# TransientsVCFG_half.net
KiCad netlist of a schematic drawn in EAGLE
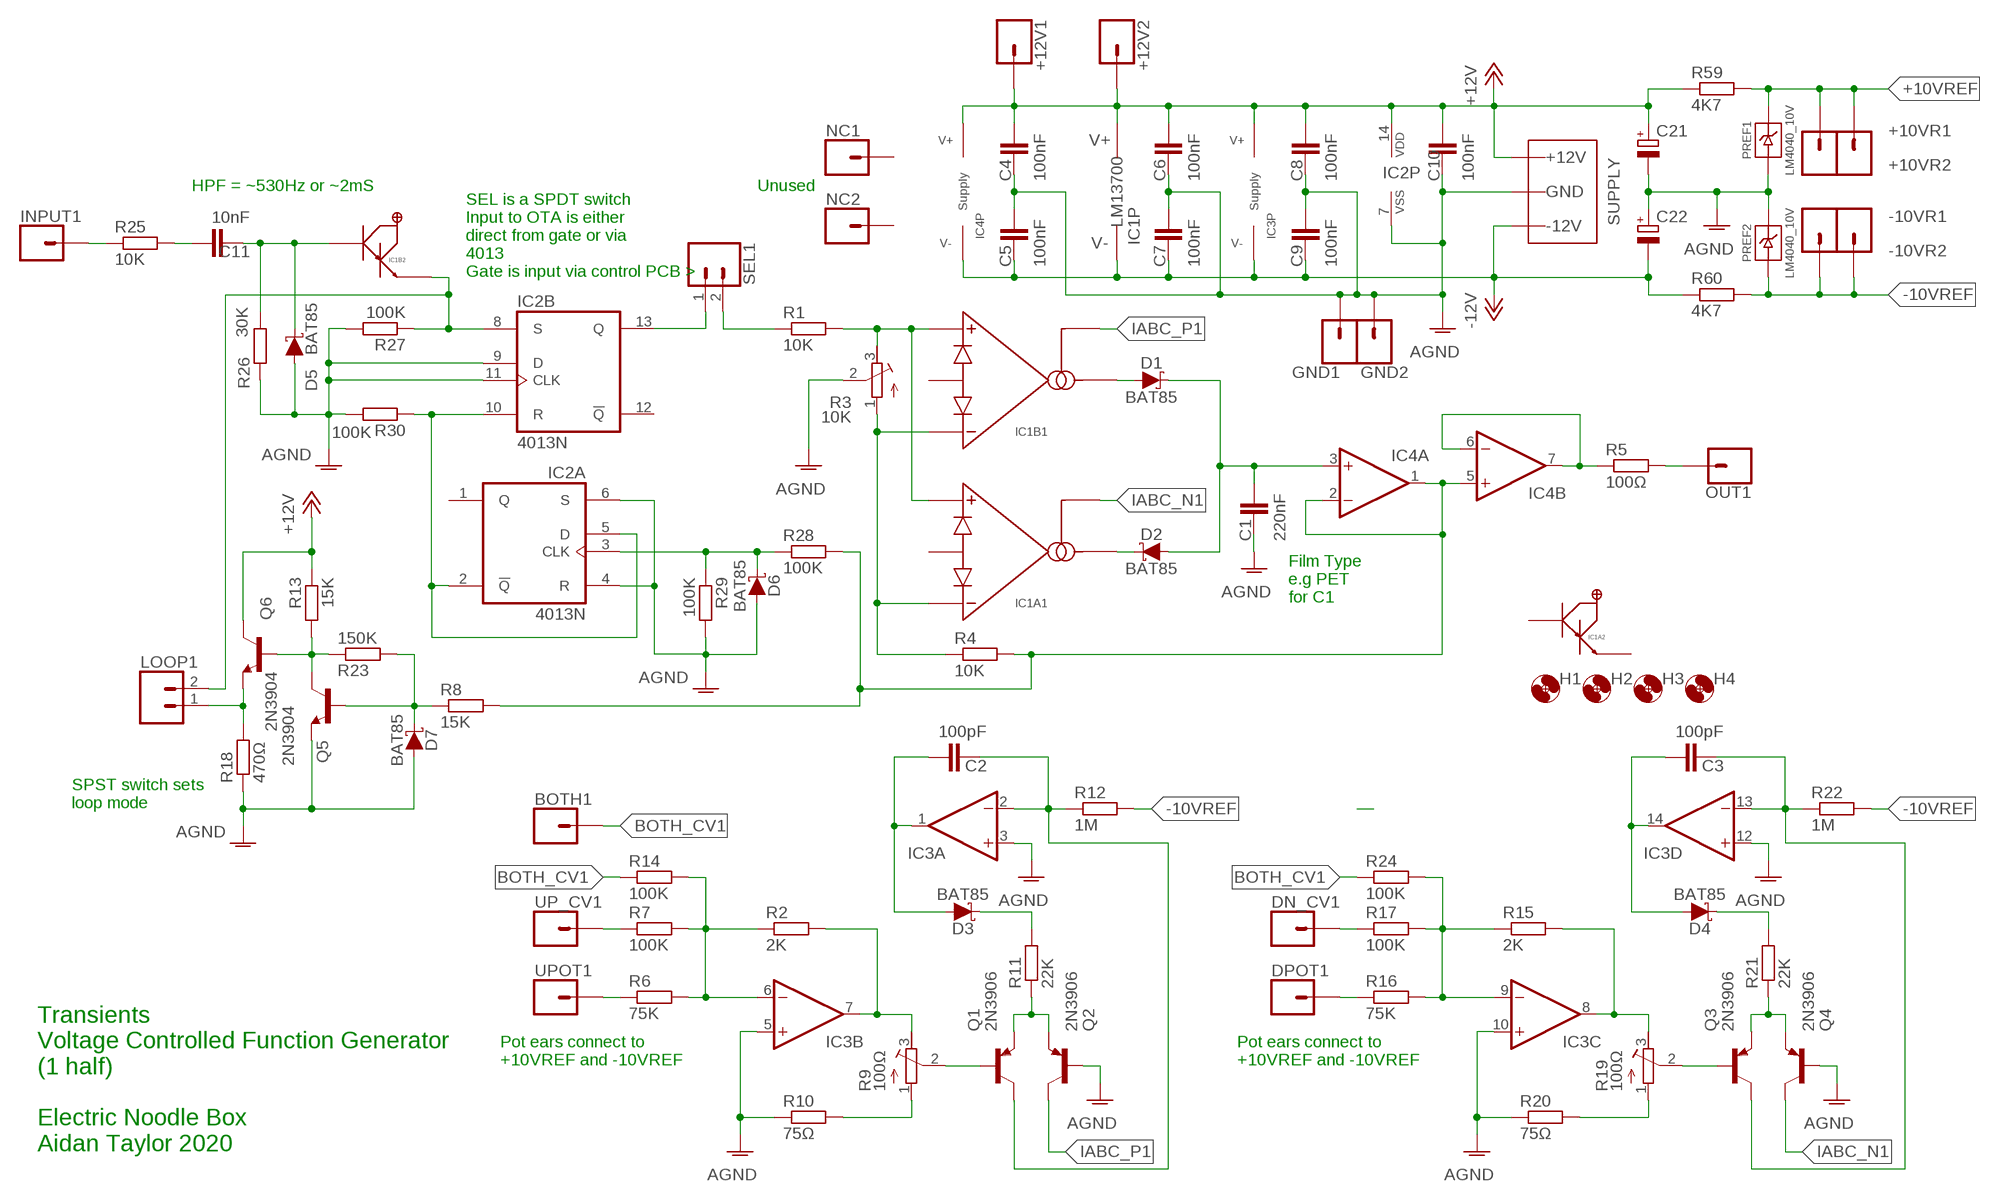
[diagram p0: schematic, sheet 1]

(export (version "E")
  (design (tool "Eeschema 10.0.6"))
  (components
    (comp (ref "+10VR1")
      (value "1XWIREPAD")
      (footprint "eagle-import:1X01")
      (libsource (lib "eagle-import") (part "1XWIREPAD"))
    )
    (comp (ref "+10VR2")
      (value "1XWIREPAD")
      (footprint "eagle-import:1X01")
      (libsource (lib "eagle-import") (part "1XWIREPAD"))
    )
    (comp (ref "+12V1")
      (value "1XWIREPAD")
      (footprint "eagle-import:1X01")
      (libsource (lib "eagle-import") (part "1XWIREPAD"))
    )
    (comp (ref "+12V2")
      (value "1XWIREPAD")
      (footprint "eagle-import:1X01")
      (libsource (lib "eagle-import") (part "1XWIREPAD"))
    )
    (comp (ref "-10VR1")
      (value "1XWIREPAD")
      (footprint "eagle-import:1X01")
      (libsource (lib "eagle-import") (part "1XWIREPAD"))
    )
    (comp (ref "-10VR2")
      (value "1XWIREPAD")
      (footprint "eagle-import:1X01")
      (libsource (lib "eagle-import") (part "1XWIREPAD"))
    )
    (comp (ref "BOTH1")
      (value "1XWIREPAD")
      (footprint "eagle-import:1X01")
      (libsource (lib "eagle-import") (part "1XWIREPAD"))
    )
    (comp (ref "C1")
      (value "220nF")
      (footprint "eagle-import:C050-025X075")
      (libsource (lib "eagle-import") (part "C-EU050-025X075"))
    )
    (comp (ref "C2")
      (value "100pF")
      (footprint "eagle-import:C050-025X075")
      (libsource (lib "eagle-import") (part "C-EU050-025X075"))
    )
    (comp (ref "C3")
      (value "100pF")
      (footprint "eagle-import:C050-025X075")
      (libsource (lib "eagle-import") (part "C-EU050-025X075"))
    )
    (comp (ref "C4")
      (value "100nF")
      (footprint "eagle-import:C050-025X075")
      (libsource (lib "eagle-import") (part "C-EU050-025X075"))
    )
    (comp (ref "C5")
      (value "100nF")
      (footprint "eagle-import:C050-025X075")
      (libsource (lib "eagle-import") (part "C-EU050-025X075"))
    )
    (comp (ref "C6")
      (value "100nF")
      (footprint "eagle-import:C050-025X075")
      (libsource (lib "eagle-import") (part "C-EU050-025X075"))
    )
    (comp (ref "C7")
      (value "100nF")
      (footprint "eagle-import:C050-025X075")
      (libsource (lib "eagle-import") (part "C-EU050-025X075"))
    )
    (comp (ref "C8")
      (value "100nF")
      (footprint "eagle-import:C050-025X075")
      (libsource (lib "eagle-import") (part "C-EU050-025X075"))
    )
    (comp (ref "C9")
      (value "100nF")
      (footprint "eagle-import:C050-025X075")
      (libsource (lib "eagle-import") (part "C-EU050-025X075"))
    )
    (comp (ref "C10")
      (value "100nF")
      (footprint "eagle-import:C050-025X075")
      (libsource (lib "eagle-import") (part "C-EU050-025X075"))
    )
    (comp (ref "C11")
      (value "10nF")
      (footprint "eagle-import:C050-025X075")
      (libsource (lib "eagle-import") (part "C-EU050-025X075"))
    )
    (comp (ref "C21")
      (value "CPOL-EUE2.5-6")
      (footprint "eagle-import:E2,5-6")
      (libsource (lib "eagle-import") (part "CPOL-EUE2.5-6"))
    )
    (comp (ref "C22")
      (value "CPOL-EUE2.5-6")
      (footprint "eagle-import:E2,5-6")
      (libsource (lib "eagle-import") (part "CPOL-EUE2.5-6"))
    )
    (comp (ref "D1")
      (value "BAT85")
      (footprint "eagle-import:DO35-7")
      (libsource (lib "eagle-import") (part "SCHOTTKY_DO35"))
    )
    (comp (ref "D2")
      (value "BAT85")
      (footprint "eagle-import:DO35-7")
      (libsource (lib "eagle-import") (part "SCHOTTKY_DO35"))
    )
    (comp (ref "D3")
      (value "BAT85")
      (footprint "eagle-import:DO35-7")
      (libsource (lib "eagle-import") (part "SCHOTTKY_DO35"))
    )
    (comp (ref "D4")
      (value "BAT85")
      (footprint "eagle-import:DO35-7")
      (libsource (lib "eagle-import") (part "SCHOTTKY_DO35"))
    )
    (comp (ref "D5")
      (value "BAT85")
      (footprint "eagle-import:DO35-7")
      (libsource (lib "eagle-import") (part "SCHOTTKY_DO35"))
    )
    (comp (ref "D6")
      (value "BAT85")
      (footprint "eagle-import:DO35-7")
      (libsource (lib "eagle-import") (part "SCHOTTKY_DO35"))
    )
    (comp (ref "D7")
      (value "BAT85")
      (footprint "eagle-import:DO35-7")
      (libsource (lib "eagle-import") (part "SCHOTTKY_DO35"))
    )
    (comp (ref "DN_CV1")
      (value "1XWIREPAD")
      (footprint "eagle-import:1X01")
      (libsource (lib "eagle-import") (part "1XWIREPAD"))
    )
    (comp (ref "DPOT1")
      (value "1XWIREPAD")
      (footprint "eagle-import:1X01")
      (libsource (lib "eagle-import") (part "1XWIREPAD"))
    )
    (comp (ref "GND1")
      (value "1XWIREPAD")
      (footprint "eagle-import:1X01")
      (libsource (lib "eagle-import") (part "1XWIREPAD"))
    )
    (comp (ref "GND2")
      (value "1XWIREPAD")
      (footprint "eagle-import:1X01")
      (libsource (lib "eagle-import") (part "1XWIREPAD"))
    )
    (comp (ref "H1")
      (value "MOUNT-HOLE3.2")
      (footprint "eagle-import:3,2")
      (libsource (lib "eagle-import") (part "MOUNT-HOLE3.2"))
    )
    (comp (ref "H2")
      (value "MOUNT-HOLE3.2")
      (footprint "eagle-import:3,2")
      (libsource (lib "eagle-import") (part "MOUNT-HOLE3.2"))
    )
    (comp (ref "H3")
      (value "MOUNT-HOLE3.2")
      (footprint "eagle-import:3,2")
      (libsource (lib "eagle-import") (part "MOUNT-HOLE3.2"))
    )
    (comp (ref "H4")
      (value "MOUNT-HOLE3.2")
      (footprint "eagle-import:3,2")
      (libsource (lib "eagle-import") (part "MOUNT-HOLE3.2"))
    )
    (comp (ref "IC1")
      (value "LM13700DIL")
      (footprint "eagle-import:DIL16")
      (libsource (lib "eagle-import") (part "LM13700DIL"))
    )
    (comp (ref "IC2")
      (value "4013N")
      (footprint "eagle-import:DIL14")
      (libsource (lib "eagle-import") (part "4013N"))
    )
    (comp (ref "IC3")
      (value "TL0X4DIL")
      (footprint "eagle-import:DIL14")
      (libsource (lib "eagle-import") (part "TL0X4DIL"))
    )
    (comp (ref "IC4")
      (value "TL0X2DIL")
      (footprint "eagle-import:DIL08")
      (libsource (lib "eagle-import") (part "TL0X2DIL"))
    )
    (comp (ref "INPUT1")
      (value "1XWIREPAD")
      (footprint "eagle-import:1X01")
      (libsource (lib "eagle-import") (part "1XWIREPAD"))
    )
    (comp (ref "LOOP1")
      (value "2XWIREPAD")
      (footprint "eagle-import:1X02")
      (libsource (lib "eagle-import") (part "2XWIREPAD"))
    )
    (comp (ref "NC1")
      (value "1XWIREPAD")
      (footprint "eagle-import:1X01")
      (libsource (lib "eagle-import") (part "1XWIREPAD"))
    )
    (comp (ref "NC2")
      (value "1XWIREPAD")
      (footprint "eagle-import:1X01")
      (libsource (lib "eagle-import") (part "1XWIREPAD"))
    )
    (comp (ref "OUT1")
      (value "1XWIREPAD")
      (footprint "eagle-import:1X01")
      (libsource (lib "eagle-import") (part "1XWIREPAD"))
    )
    (comp (ref "PREF1")
      (value "LM4040_10V")
      (footprint "eagle-import:TO92")
      (libsource (lib "eagle-import") (part "LM4040TH"))
    )
    (comp (ref "PREF2")
      (value "LM4040_10V")
      (footprint "eagle-import:TO92")
      (libsource (lib "eagle-import") (part "LM4040TH"))
    )
    (comp (ref "Q1")
      (value "2N3906")
      (footprint "eagle-import:TO92")
      (libsource (lib "eagle-import") (part "2N3906"))
    )
    (comp (ref "Q2")
      (value "2N3906")
      (footprint "eagle-import:TO92")
      (libsource (lib "eagle-import") (part "2N3906"))
    )
    (comp (ref "Q3")
      (value "2N3906")
      (footprint "eagle-import:TO92")
      (libsource (lib "eagle-import") (part "2N3906"))
    )
    (comp (ref "Q4")
      (value "2N3906")
      (footprint "eagle-import:TO92")
      (libsource (lib "eagle-import") (part "2N3906"))
    )
    (comp (ref "Q5")
      (value "2N3904")
      (footprint "eagle-import:TO92")
      (libsource (lib "eagle-import") (part "2N3904"))
    )
    (comp (ref "Q6")
      (value "2N3904")
      (footprint "eagle-import:TO92")
      (libsource (lib "eagle-import") (part "2N3904"))
    )
    (comp (ref "R1")
      (value "10K")
      (footprint "eagle-import:0207_10")
      (libsource (lib "eagle-import") (part "R-EU_0207/10"))
    )
    (comp (ref "R2")
      (value "2K")
      (footprint "eagle-import:0207_10")
      (libsource (lib "eagle-import") (part "R-EU_0207/10"))
    )
    (comp (ref "R3")
      (value "10K")
      (footprint "eagle-import:RTRIM3296W")
      (libsource (lib "eagle-import") (part "R-TRIMM3296W"))
    )
    (comp (ref "R4")
      (value "10K")
      (footprint "eagle-import:0207_10")
      (libsource (lib "eagle-import") (part "R-EU_0207/10"))
    )
    (comp (ref "R5")
      (value "100Ω")
      (footprint "eagle-import:0207_10")
      (libsource (lib "eagle-import") (part "R-EU_0207/10"))
    )
    (comp (ref "R6")
      (value "75K")
      (footprint "eagle-import:0207_10")
      (libsource (lib "eagle-import") (part "R-EU_0207/10"))
    )
    (comp (ref "R7")
      (value "100K")
      (footprint "eagle-import:0207_10")
      (libsource (lib "eagle-import") (part "R-EU_0207/10"))
    )
    (comp (ref "R8")
      (value "15K")
      (footprint "eagle-import:0207_10")
      (libsource (lib "eagle-import") (part "R-EU_0207/10"))
    )
    (comp (ref "R9")
      (value "100Ω")
      (footprint "eagle-import:RTRIM3296W")
      (libsource (lib "eagle-import") (part "R-TRIMM3296W"))
    )
    (comp (ref "R10")
      (value "75Ω")
      (footprint "eagle-import:0207_10")
      (libsource (lib "eagle-import") (part "R-EU_0207/10"))
    )
    (comp (ref "R11")
      (value "22K")
      (footprint "eagle-import:0207_10")
      (libsource (lib "eagle-import") (part "R-EU_0207/10"))
    )
    (comp (ref "R12")
      (value "1M")
      (footprint "eagle-import:0207_10")
      (libsource (lib "eagle-import") (part "R-EU_0207/10"))
    )
    (comp (ref "R13")
      (value "15K")
      (footprint "eagle-import:0207_10")
      (libsource (lib "eagle-import") (part "R-EU_0207/10"))
    )
    (comp (ref "R14")
      (value "100K")
      (footprint "eagle-import:0207_10")
      (libsource (lib "eagle-import") (part "R-EU_0207/10"))
    )
    (comp (ref "R15")
      (value "2K")
      (footprint "eagle-import:0207_10")
      (libsource (lib "eagle-import") (part "R-EU_0207/10"))
    )
    (comp (ref "R16")
      (value "75K")
      (footprint "eagle-import:0207_10")
      (libsource (lib "eagle-import") (part "R-EU_0207/10"))
    )
    (comp (ref "R17")
      (value "100K")
      (footprint "eagle-import:0207_10")
      (libsource (lib "eagle-import") (part "R-EU_0207/10"))
    )
    (comp (ref "R18")
      (value "470Ω")
      (footprint "eagle-import:0207_10")
      (libsource (lib "eagle-import") (part "R-EU_0207/10"))
    )
    (comp (ref "R19")
      (value "100Ω")
      (footprint "eagle-import:RTRIM3296W")
      (libsource (lib "eagle-import") (part "R-TRIMM3296W"))
    )
    (comp (ref "R20")
      (value "75Ω")
      (footprint "eagle-import:0207_10")
      (libsource (lib "eagle-import") (part "R-EU_0207/10"))
    )
    (comp (ref "R21")
      (value "22K")
      (footprint "eagle-import:0207_10")
      (libsource (lib "eagle-import") (part "R-EU_0207/10"))
    )
    (comp (ref "R22")
      (value "1M")
      (footprint "eagle-import:0207_10")
      (libsource (lib "eagle-import") (part "R-EU_0207/10"))
    )
    (comp (ref "R23")
      (value "150K")
      (footprint "eagle-import:0207_10")
      (libsource (lib "eagle-import") (part "R-EU_0207/10"))
    )
    (comp (ref "R24")
      (value "100K")
      (footprint "eagle-import:0207_10")
      (libsource (lib "eagle-import") (part "R-EU_0207/10"))
    )
    (comp (ref "R25")
      (value "10K")
      (footprint "eagle-import:0207_10")
      (libsource (lib "eagle-import") (part "R-EU_0207/10"))
    )
    (comp (ref "R26")
      (value "30K")
      (footprint "eagle-import:0207_10")
      (libsource (lib "eagle-import") (part "R-EU_0207/10"))
    )
    (comp (ref "R27")
      (value "100K")
      (footprint "eagle-import:0207_10")
      (libsource (lib "eagle-import") (part "R-EU_0207/10"))
    )
    (comp (ref "R28")
      (value "100K")
      (footprint "eagle-import:0207_10")
      (libsource (lib "eagle-import") (part "R-EU_0207/10"))
    )
    (comp (ref "R29")
      (value "100K")
      (footprint "eagle-import:0207_10")
      (libsource (lib "eagle-import") (part "R-EU_0207/10"))
    )
    (comp (ref "R30")
      (value "100K")
      (footprint "eagle-import:0207_10")
      (libsource (lib "eagle-import") (part "R-EU_0207/10"))
    )
    (comp (ref "R59")
      (value "4K7")
      (footprint "eagle-import:0207_10")
      (libsource (lib "eagle-import") (part "R-EU_0207/10"))
    )
    (comp (ref "R60")
      (value "4K7")
      (footprint "eagle-import:0207_10")
      (libsource (lib "eagle-import") (part "R-EU_0207/10"))
    )
    (comp (ref "SEL1")
      (value "2XWIREPAD")
      (footprint "eagle-import:1X02")
      (libsource (lib "eagle-import") (part "2XWIREPAD"))
    )
    (comp (ref "UPOT1")
      (value "1XWIREPAD")
      (footprint "eagle-import:1X01")
      (libsource (lib "eagle-import") (part "1XWIREPAD"))
    )
    (comp (ref "UP_CV1")
      (value "1XWIREPAD")
      (footprint "eagle-import:1X01")
      (libsource (lib "eagle-import") (part "1XWIREPAD"))
    )
    (comp (ref "WP1")
      (value "COMBO_SUPPLY_HEADER")
      (footprint "eagle-import:COMBINED_POWER")
      (libsource (lib "eagle-import") (part "COMBO_SUPPLY_HEADER"))
    )
  )
  (nets
    (net (code "1") (name "+10VREF") (class "Default")
      (node (ref "+10VR1") (pin "1") (pinfunction "1_1") (pintype "passive"))
      (node (ref "+10VR2") (pin "1") (pinfunction "1_1") (pintype "passive"))
      (node (ref "PREF1") (pin "2") (pinfunction "CATHODE_2") (pintype "power_in"))
      (node (ref "R59") (pin "2") (pinfunction "2_2") (pintype "passive"))
    )
    (net (code "2") (name "+12V") (class "Default")
      (node (ref "+12V1") (pin "1") (pinfunction "1_1") (pintype "passive"))
      (node (ref "+12V2") (pin "1") (pinfunction "1_1") (pintype "passive"))
      (node (ref "C10") (pin "1") (pinfunction "1_1") (pintype "passive"))
      (node (ref "C21") (pin "+") (pinfunction "+_+") (pintype "passive"))
      (node (ref "C4") (pin "1") (pinfunction "1_1") (pintype "passive"))
      (node (ref "C6") (pin "1") (pinfunction "1_1") (pintype "passive"))
      (node (ref "C8") (pin "1") (pinfunction "1_1") (pintype "passive"))
      (node (ref "IC1") (pin "11") (pinfunction "V+_11") (pintype "power_in"))
      (node (ref "IC2") (pin "14") (pinfunction "VDD_14") (pintype "power_in"))
      (node (ref "IC3") (pin "4") (pinfunction "V+_4") (pintype "bidirectional"))
      (node (ref "IC4") (pin "8") (pinfunction "V+_8") (pintype "bidirectional"))
      (node (ref "Q6") (pin "1") (pinfunction "C_1") (pintype "passive"))
      (node (ref "R13") (pin "1") (pinfunction "1_1") (pintype "passive"))
      (node (ref "R59") (pin "1") (pinfunction "1_1") (pintype "passive"))
      (node (ref "WP1") (pin "V+1") (pinfunction "V++_V+1") (pintype "power_in"))
      (node (ref "WP1") (pin "V+2") (pinfunction "V++_V+2") (pintype "power_in"))
      (node (ref "WP1") (pin "V+3") (pinfunction "V++_V+3") (pintype "power_in"))
    )
    (net (code "3") (name "-10VREF") (class "Default")
      (node (ref "-10VR1") (pin "1") (pinfunction "1_1") (pintype "passive"))
      (node (ref "-10VR2") (pin "1") (pinfunction "1_1") (pintype "passive"))
      (node (ref "PREF2") (pin "3") (pinfunction "ANODE_3") (pintype "power_in"))
      (node (ref "R12") (pin "2") (pinfunction "2_2") (pintype "passive"))
      (node (ref "R22") (pin "2") (pinfunction "2_2") (pintype "passive"))
      (node (ref "R60") (pin "2") (pinfunction "2_2") (pintype "passive"))
    )
    (net (code "4") (name "-12V") (class "Default")
      (node (ref "C22") (pin "-") (pinfunction "-_-") (pintype "passive"))
      (node (ref "C5") (pin "2") (pinfunction "2_2") (pintype "passive"))
      (node (ref "C7") (pin "2") (pinfunction "2_2") (pintype "passive"))
      (node (ref "C9") (pin "2") (pinfunction "2_2") (pintype "passive"))
      (node (ref "IC1") (pin "6") (pinfunction "V-_6") (pintype "power_in"))
      (node (ref "IC3") (pin "11") (pinfunction "V-_11") (pintype "bidirectional"))
      (node (ref "IC4") (pin "4") (pinfunction "V-_4") (pintype "bidirectional"))
      (node (ref "R60") (pin "1") (pinfunction "1_1") (pintype "passive"))
      (node (ref "WP1") (pin "V-1") (pinfunction "V--_V-1") (pintype "power_in"))
      (node (ref "WP1") (pin "V-2") (pinfunction "V--_V-2") (pintype "power_in"))
      (node (ref "WP1") (pin "V-3") (pinfunction "V--_V-3") (pintype "power_in"))
    )
    (net (code "5") (name "AGND") (class "Default")
      (node (ref "C1") (pin "2") (pinfunction "2_2") (pintype "passive"))
      (node (ref "C10") (pin "2") (pinfunction "2_2") (pintype "passive"))
      (node (ref "C21") (pin "-") (pinfunction "-_-") (pintype "passive"))
      (node (ref "C22") (pin "+") (pinfunction "+_+") (pintype "passive"))
      (node (ref "C4") (pin "2") (pinfunction "2_2") (pintype "passive"))
      (node (ref "C5") (pin "1") (pinfunction "1_1") (pintype "passive"))
      (node (ref "C6") (pin "2") (pinfunction "2_2") (pintype "passive"))
      (node (ref "C7") (pin "1") (pinfunction "1_1") (pintype "passive"))
      (node (ref "C8") (pin "2") (pinfunction "2_2") (pintype "passive"))
      (node (ref "C9") (pin "1") (pinfunction "1_1") (pintype "passive"))
      (node (ref "D5") (pin "A") (pinfunction "A_A") (pintype "passive"))
      (node (ref "D6") (pin "A") (pinfunction "A_A") (pintype "passive"))
      (node (ref "D7") (pin "A") (pinfunction "A_A") (pintype "passive"))
      (node (ref "GND1") (pin "1") (pinfunction "1_1") (pintype "passive"))
      (node (ref "GND2") (pin "1") (pinfunction "1_1") (pintype "passive"))
      (node (ref "IC2") (pin "11") (pinfunction "CLK_11") (pintype "input"))
      (node (ref "IC2") (pin "4") (pinfunction "R_4") (pintype "input"))
      (node (ref "IC2") (pin "6") (pinfunction "S_6") (pintype "input"))
      (node (ref "IC2") (pin "7") (pinfunction "VSS_7") (pintype "power_in"))
      (node (ref "IC2") (pin "9") (pinfunction "D_9") (pintype "input"))
      (node (ref "IC3") (pin "10") (pinfunction "+IN_10") (pintype "input"))
      (node (ref "IC3") (pin "12") (pinfunction "+IN_12") (pintype "input"))
      (node (ref "IC3") (pin "3") (pinfunction "+IN_3") (pintype "input"))
      (node (ref "IC3") (pin "5") (pinfunction "+IN_5") (pintype "input"))
      (node (ref "PREF1") (pin "3") (pinfunction "ANODE_3") (pintype "power_in"))
      (node (ref "PREF2") (pin "2") (pinfunction "CATHODE_2") (pintype "power_in"))
      (node (ref "Q2") (pin "2") (pinfunction "B_2") (pintype "passive"))
      (node (ref "Q4") (pin "2") (pinfunction "B_2") (pintype "passive"))
      (node (ref "Q5") (pin "3") (pinfunction "E_3") (pintype "passive"))
      (node (ref "R10") (pin "1") (pinfunction "1_1") (pintype "passive"))
      (node (ref "R18") (pin "1") (pinfunction "1_1") (pintype "passive"))
      (node (ref "R20") (pin "1") (pinfunction "1_1") (pintype "passive"))
      (node (ref "R26") (pin "1") (pinfunction "1_1") (pintype "passive"))
      (node (ref "R27") (pin "2") (pinfunction "2_2") (pintype "passive"))
      (node (ref "R29") (pin "2") (pinfunction "2_2") (pintype "passive"))
      (node (ref "R3") (pin "2") (pinfunction "S_2") (pintype "passive"))
      (node (ref "R30") (pin "2") (pinfunction "2_2") (pintype "passive"))
      (node (ref "WP1") (pin "GND1") (pinfunction "AGND_GND1") (pintype "power_in"))
      (node (ref "WP1") (pin "GND2") (pinfunction "AGND_GND2") (pintype "power_in"))
      (node (ref "WP1") (pin "GND3") (pinfunction "AGND_GND3") (pintype "power_in"))
      (node (ref "WP1") (pin "GND4") (pinfunction "AGND_GND4") (pintype "power_in"))
      (node (ref "WP1") (pin "GND5") (pinfunction "AGND_GND5") (pintype "power_in"))
      (node (ref "WP1") (pin "GND6") (pinfunction "AGND_GND6") (pintype "power_in"))
      (node (ref "WP1") (pin "GND7") (pinfunction "AGND_GND7") (pintype "power_in"))
      (node (ref "WP1") (pin "GND8") (pinfunction "AGND_GND8") (pintype "power_in"))
    )
    (net (code "6") (name "BOTH_CV1") (class "Default")
      (node (ref "BOTH1") (pin "1") (pinfunction "1_1") (pintype "passive"))
      (node (ref "R14") (pin "1") (pinfunction "1_1") (pintype "passive"))
      (node (ref "R24") (pin "1") (pinfunction "1_1") (pintype "passive"))
    )
    (net (code "7") (name "IABC_N1") (class "Default")
      (node (ref "IC1") (pin "1") (pinfunction "AMPBIAS_1") (pintype "input"))
      (node (ref "Q4") (pin "1") (pinfunction "C_1") (pintype "passive"))
    )
    (net (code "8") (name "IABC_P1") (class "Default")
      (node (ref "IC1") (pin "16") (pinfunction "AMPBIAS_16") (pintype "input"))
      (node (ref "Q2") (pin "1") (pinfunction "C_1") (pintype "passive"))
    )
    (net (code "9") (name "Net-(C11-Pad1)") (class "Default")
      (node (ref "C11") (pin "1") (pinfunction "1_1") (pintype "passive"))
      (node (ref "R25") (pin "2") (pinfunction "2_2") (pintype "passive"))
    )
    (net (code "10") (name "Net-(D3-PadC)") (class "Default")
      (node (ref "D3") (pin "C") (pinfunction "C_C") (pintype "passive"))
      (node (ref "R11") (pin "2") (pinfunction "2_2") (pintype "passive"))
    )
    (net (code "11") (name "Net-(D4-PadC)") (class "Default")
      (node (ref "D4") (pin "C") (pinfunction "C_C") (pintype "passive"))
      (node (ref "R21") (pin "2") (pinfunction "2_2") (pintype "passive"))
    )
    (net (code "12") (name "Net-(DN_CV1-Pad1)") (class "Default")
      (node (ref "DN_CV1") (pin "1") (pinfunction "1_1") (pintype "passive"))
      (node (ref "R17") (pin "1") (pinfunction "1_1") (pintype "passive"))
    )
    (net (code "13") (name "Net-(DPOT1-Pad1)") (class "Default")
      (node (ref "DPOT1") (pin "1") (pinfunction "1_1") (pintype "passive"))
      (node (ref "R16") (pin "1") (pinfunction "1_1") (pintype "passive"))
    )
    (net (code "14") (name "Net-(IC1A-AMP+)") (class "Default")
      (node (ref "IC1") (pin "14") (pinfunction "AMP+_14") (pintype "input"))
      (node (ref "IC1") (pin "3") (pinfunction "AMP+_3") (pintype "input"))
      (node (ref "R1") (pin "2") (pinfunction "2_2") (pintype "passive"))
      (node (ref "R3") (pin "3") (pinfunction "E_3") (pintype "passive"))
    )
    (net (code "15") (name "Net-(IC1A-AMP-)") (class "Default")
      (node (ref "IC1") (pin "13") (pinfunction "AMP-_13") (pintype "input"))
      (node (ref "IC1") (pin "4") (pinfunction "AMP-_4") (pintype "input"))
      (node (ref "R3") (pin "1") (pinfunction "A_1") (pintype "passive"))
      (node (ref "R4") (pin "1") (pinfunction "1_1") (pintype "passive"))
    )
    (net (code "16") (name "Net-(IC1A-AMPOUT)") (class "Default")
      (node (ref "D2") (pin "C") (pinfunction "C_C") (pintype "passive"))
      (node (ref "IC1") (pin "5") (pinfunction "AMPOUT_5") (pintype "output"))
    )
    (net (code "17") (name "Net-(IC1C-AMPOUT)") (class "Default")
      (node (ref "D1") (pin "A") (pinfunction "A_A") (pintype "passive"))
      (node (ref "IC1") (pin "12") (pinfunction "AMPOUT_12") (pintype "output"))
    )
    (net (code "18") (name "Net-(IC1D-BUFF_IN)") (class "Default")
      (node (ref "C11") (pin "2") (pinfunction "2_2") (pintype "passive"))
      (node (ref "D5") (pin "C") (pinfunction "C_C") (pintype "passive"))
      (node (ref "IC1") (pin "10") (pinfunction "BUFF_IN_10") (pintype "input"))
      (node (ref "R26") (pin "2") (pinfunction "2_2") (pintype "passive"))
    )
    (net (code "19") (name "Net-(IC1D-BUFF_OUT)") (class "Default")
      (node (ref "IC1") (pin "9") (pinfunction "BUFF_OUT_9") (pintype "bidirectional"))
      (node (ref "IC2") (pin "8") (pinfunction "S_8") (pintype "input"))
      (node (ref "LOOP1") (pin "2") (pinfunction "2_2") (pintype "passive"))
      (node (ref "R27") (pin "1") (pinfunction "1_1") (pintype "passive"))
    )
    (net (code "20") (name "Net-(IC2A-CLK)") (class "Default")
      (node (ref "D6") (pin "C") (pinfunction "C_C") (pintype "passive"))
      (node (ref "IC2") (pin "3") (pinfunction "CLK_3") (pintype "input"))
      (node (ref "R28") (pin "1") (pinfunction "1_1") (pintype "passive"))
      (node (ref "R29") (pin "1") (pinfunction "1_1") (pintype "passive"))
    )
    (net (code "21") (name "Net-(IC2A-D)") (class "Default")
      (node (ref "IC2") (pin "10") (pinfunction "R_10") (pintype "input"))
      (node (ref "IC2") (pin "2") (pinfunction "~{Q}_2") (pintype "output"))
      (node (ref "IC2") (pin "5") (pinfunction "D_5") (pintype "input"))
      (node (ref "R30") (pin "1") (pinfunction "1_1") (pintype "passive"))
    )
    (net (code "22") (name "Net-(IC2B-Q)") (class "Default")
      (node (ref "IC2") (pin "13") (pinfunction "Q_13") (pintype "output"))
      (node (ref "SEL1") (pin "1") (pinfunction "1_1") (pintype "passive"))
    )
    (net (code "23") (name "Net-(IC3A--IN)") (class "Default")
      (node (ref "C2") (pin "2") (pinfunction "2_2") (pintype "passive"))
      (node (ref "IC3") (pin "2") (pinfunction "-IN_2") (pintype "input"))
      (node (ref "Q1") (pin "1") (pinfunction "C_1") (pintype "passive"))
      (node (ref "R12") (pin "1") (pinfunction "1_1") (pintype "passive"))
    )
    (net (code "24") (name "Net-(IC3A-OUT)") (class "Default")
      (node (ref "C2") (pin "1") (pinfunction "1_1") (pintype "passive"))
      (node (ref "D3") (pin "A") (pinfunction "A_A") (pintype "passive"))
      (node (ref "IC3") (pin "1") (pinfunction "OUT_1") (pintype "output"))
    )
    (net (code "25") (name "Net-(IC3B--IN)") (class "Default")
      (node (ref "IC3") (pin "6") (pinfunction "-IN_6") (pintype "input"))
      (node (ref "R14") (pin "2") (pinfunction "2_2") (pintype "passive"))
      (node (ref "R2") (pin "1") (pinfunction "1_1") (pintype "passive"))
      (node (ref "R6") (pin "2") (pinfunction "2_2") (pintype "passive"))
      (node (ref "R7") (pin "2") (pinfunction "2_2") (pintype "passive"))
    )
    (net (code "26") (name "Net-(IC3B-OUT)") (class "Default")
      (node (ref "IC3") (pin "7") (pinfunction "OUT_7") (pintype "output"))
      (node (ref "R2") (pin "2") (pinfunction "2_2") (pintype "passive"))
      (node (ref "R9") (pin "3") (pinfunction "E_3") (pintype "passive"))
    )
    (net (code "27") (name "Net-(IC3C--IN)") (class "Default")
      (node (ref "IC3") (pin "9") (pinfunction "-IN_9") (pintype "input"))
      (node (ref "R15") (pin "1") (pinfunction "1_1") (pintype "passive"))
      (node (ref "R16") (pin "2") (pinfunction "2_2") (pintype "passive"))
      (node (ref "R17") (pin "2") (pinfunction "2_2") (pintype "passive"))
      (node (ref "R24") (pin "2") (pinfunction "2_2") (pintype "passive"))
    )
    (net (code "28") (name "Net-(IC3C-OUT)") (class "Default")
      (node (ref "IC3") (pin "8") (pinfunction "OUT_8") (pintype "output"))
      (node (ref "R15") (pin "2") (pinfunction "2_2") (pintype "passive"))
      (node (ref "R19") (pin "3") (pinfunction "E_3") (pintype "passive"))
    )
    (net (code "29") (name "Net-(IC3D--IN)") (class "Default")
      (node (ref "C3") (pin "2") (pinfunction "2_2") (pintype "passive"))
      (node (ref "IC3") (pin "13") (pinfunction "-IN_13") (pintype "input"))
      (node (ref "Q3") (pin "1") (pinfunction "C_1") (pintype "passive"))
      (node (ref "R22") (pin "1") (pinfunction "1_1") (pintype "passive"))
    )
    (net (code "30") (name "Net-(IC3D-OUT)") (class "Default")
      (node (ref "C3") (pin "1") (pinfunction "1_1") (pintype "passive"))
      (node (ref "D4") (pin "A") (pinfunction "A_A") (pintype "passive"))
      (node (ref "IC3") (pin "14") (pinfunction "OUT_14") (pintype "output"))
    )
    (net (code "31") (name "Net-(IC4A-+IN)") (class "Default")
      (node (ref "C1") (pin "1") (pinfunction "1_1") (pintype "passive"))
      (node (ref "D1") (pin "C") (pinfunction "C_C") (pintype "passive"))
      (node (ref "D2") (pin "A") (pinfunction "A_A") (pintype "passive"))
      (node (ref "IC4") (pin "3") (pinfunction "+IN_3") (pintype "input"))
    )
    (net (code "32") (name "Net-(IC4A--IN)") (class "Default")
      (node (ref "IC4") (pin "1") (pinfunction "OUT_1") (pintype "output"))
      (node (ref "IC4") (pin "2") (pinfunction "-IN_2") (pintype "input"))
      (node (ref "IC4") (pin "5") (pinfunction "+IN_5") (pintype "input"))
      (node (ref "R28") (pin "2") (pinfunction "2_2") (pintype "passive"))
      (node (ref "R4") (pin "2") (pinfunction "2_2") (pintype "passive"))
      (node (ref "R8") (pin "2") (pinfunction "2_2") (pintype "passive"))
    )
    (net (code "33") (name "Net-(IC4B--IN)") (class "Default")
      (node (ref "IC4") (pin "6") (pinfunction "-IN_6") (pintype "input"))
      (node (ref "IC4") (pin "7") (pinfunction "OUT_7") (pintype "output"))
      (node (ref "R5") (pin "1") (pinfunction "1_1") (pintype "passive"))
    )
    (net (code "34") (name "Net-(INPUT1-Pad1)") (class "Default")
      (node (ref "INPUT1") (pin "1") (pinfunction "1_1") (pintype "passive"))
      (node (ref "R25") (pin "1") (pinfunction "1_1") (pintype "passive"))
    )
    (net (code "35") (name "Net-(OUT1-Pad1)") (class "Default")
      (node (ref "OUT1") (pin "1") (pinfunction "1_1") (pintype "passive"))
      (node (ref "R5") (pin "2") (pinfunction "2_2") (pintype "passive"))
    )
    (net (code "36") (name "Net-(Q1-B)") (class "Default")
      (node (ref "Q1") (pin "2") (pinfunction "B_2") (pintype "passive"))
      (node (ref "R9") (pin "2") (pinfunction "S_2") (pintype "passive"))
    )
    (net (code "37") (name "Net-(Q1-E)") (class "Default")
      (node (ref "Q1") (pin "3") (pinfunction "E_3") (pintype "passive"))
      (node (ref "Q2") (pin "3") (pinfunction "E_3") (pintype "passive"))
      (node (ref "R11") (pin "1") (pinfunction "1_1") (pintype "passive"))
    )
    (net (code "38") (name "Net-(Q3-B)") (class "Default")
      (node (ref "Q3") (pin "2") (pinfunction "B_2") (pintype "passive"))
      (node (ref "R19") (pin "2") (pinfunction "S_2") (pintype "passive"))
    )
    (net (code "39") (name "Net-(Q3-E)") (class "Default")
      (node (ref "Q3") (pin "3") (pinfunction "E_3") (pintype "passive"))
      (node (ref "Q4") (pin "3") (pinfunction "E_3") (pintype "passive"))
      (node (ref "R21") (pin "1") (pinfunction "1_1") (pintype "passive"))
    )
    (net (code "40") (name "Net-(Q5-B)") (class "Default")
      (node (ref "D7") (pin "C") (pinfunction "C_C") (pintype "passive"))
      (node (ref "Q5") (pin "2") (pinfunction "B_2") (pintype "passive"))
      (node (ref "R23") (pin "2") (pinfunction "2_2") (pintype "passive"))
      (node (ref "R8") (pin "1") (pinfunction "1_1") (pintype "passive"))
    )
    (net (code "41") (name "Net-(Q5-C)") (class "Default")
      (node (ref "Q5") (pin "1") (pinfunction "C_1") (pintype "passive"))
      (node (ref "Q6") (pin "2") (pinfunction "B_2") (pintype "passive"))
      (node (ref "R13") (pin "2") (pinfunction "2_2") (pintype "passive"))
      (node (ref "R23") (pin "1") (pinfunction "1_1") (pintype "passive"))
    )
    (net (code "42") (name "Net-(Q6-E)") (class "Default")
      (node (ref "LOOP1") (pin "1") (pinfunction "1_1") (pintype "passive"))
      (node (ref "Q6") (pin "3") (pinfunction "E_3") (pintype "passive"))
      (node (ref "R18") (pin "2") (pinfunction "2_2") (pintype "passive"))
    )
    (net (code "43") (name "Net-(R1-Pad1)") (class "Default")
      (node (ref "R1") (pin "1") (pinfunction "1_1") (pintype "passive"))
      (node (ref "SEL1") (pin "2") (pinfunction "2_2") (pintype "passive"))
    )
    (net (code "44") (name "Net-(R6-Pad1)") (class "Default")
      (node (ref "R6") (pin "1") (pinfunction "1_1") (pintype "passive"))
      (node (ref "UPOT1") (pin "1") (pinfunction "1_1") (pintype "passive"))
    )
    (net (code "45") (name "Net-(R7-Pad1)") (class "Default")
      (node (ref "R7") (pin "1") (pinfunction "1_1") (pintype "passive"))
      (node (ref "UP_CV1") (pin "1") (pinfunction "1_1") (pintype "passive"))
    )
    (net (code "46") (name "Net-(R9-A)") (class "Default")
      (node (ref "R10") (pin "2") (pinfunction "2_2") (pintype "passive"))
      (node (ref "R9") (pin "1") (pinfunction "A_1") (pintype "passive"))
    )
    (net (code "47") (name "Net-(R19-A)") (class "Default")
      (node (ref "R19") (pin "1") (pinfunction "A_1") (pintype "passive"))
      (node (ref "R20") (pin "2") (pinfunction "2_2") (pintype "passive"))
    )
    (net (code "48") (name "unconnected-(IC1A-DIODES-Pad2)") (class "Default")
      (node (ref "IC1") (pin "2") (pinfunction "DIODES_2") (pintype "input"))
    )
    (net (code "49") (name "unconnected-(IC1B-BUFF_IN-Pad7)") (class "Default")
      (node (ref "IC1") (pin "7") (pinfunction "BUFF_IN_7") (pintype "input"))
    )
    (net (code "50") (name "unconnected-(IC1B-BUFF_OUT-Pad8)") (class "Default")
      (node (ref "IC1") (pin "8") (pinfunction "BUFF_OUT_8") (pintype "bidirectional"))
    )
    (net (code "51") (name "unconnected-(IC1C-DIODES-Pad15)") (class "Default")
      (node (ref "IC1") (pin "15") (pinfunction "DIODES_15") (pintype "input"))
    )
    (net (code "52") (name "unconnected-(IC2A-Q-Pad1)") (class "Default")
      (node (ref "IC2") (pin "1") (pinfunction "Q_1") (pintype "output"))
    )
    (net (code "53") (name "unconnected-(IC2B-~{Q}-Pad12)") (class "Default")
      (node (ref "IC2") (pin "12") (pinfunction "~{Q}_12") (pintype "output"))
    )
    (net (code "54") (name "unconnected-(NC1-Pad1)") (class "Default")
      (node (ref "NC1") (pin "1") (pinfunction "1_1") (pintype "passive"))
    )
    (net (code "55") (name "unconnected-(NC2-Pad1)") (class "Default")
      (node (ref "NC2") (pin "1") (pinfunction "1_1") (pintype "passive"))
    )
  )
)
